# rgb_led.net
KiCad netlist of a schematic drawn in Altium Designer
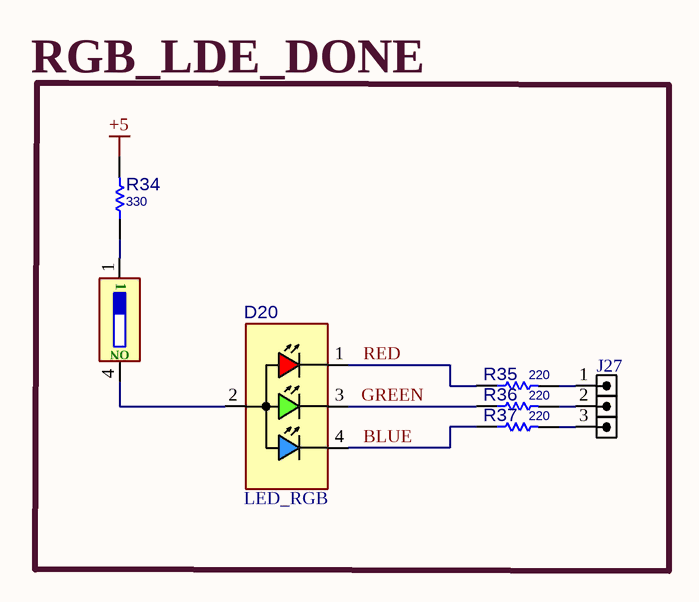
[diagram p0: rgb_led.SchDoc]

(export (version "E")
  (design (tool "Eeschema 10.0.6"))
  (components
    (comp (ref "D20")
      (value "LED_RGB")
      (footprint "LED5RGB")
      (description "LED, THD, 5MM, RGB COMMON CATHODE")
      (fields (field (name "MANF_P#") "YSL-R596CR3G4B5C-C10") (field (name "MANF") "CHINA YOUNG"))
      (libsource (lib "led(diode)") (part "LED_THD_5MM_RGB_CA"))
    )
    (comp (ref "J27")
      (value "HDRM3")
      (footprint "HDR_M_1X3")
      (description "CONN, HEADER, Male, pitch: 2.54mm, 3POS")
      (libsource (lib "conn_header_2.54mm_st") (part "HDR_M_1X3"))
    )
    (comp (ref "R34")
      (value "330")
      (footprint "R025W_AX04")
      (description "RESISTOR, THD")
      (fields (field (name "MANF_P#") "RK73H1ETTP4701F") (field (name "MANF") "KOA SPEER"))
      (libsource (lib "passive_thd") (part "RES_THD"))
    )
    (comp (ref "R35")
      (value "220")
      (footprint "R025W_AX04")
      (description "RESISTOR, THD")
      (fields (field (name "MANF_P#") "RK73H1ETTP4701F") (field (name "MANF") "KOA SPEER"))
      (libsource (lib "passive_thd") (part "RES_THD"))
    )
    (comp (ref "R36")
      (value "220")
      (footprint "R025W_AX04")
      (description "RESISTOR, THD")
      (fields (field (name "MANF_P#") "RK73H1ETTP4701F") (field (name "MANF") "KOA SPEER"))
      (libsource (lib "passive_thd") (part "RES_THD"))
    )
    (comp (ref "R37")
      (value "220")
      (footprint "R025W_AX04")
      (description "RESISTOR, THD")
      (fields (field (name "MANF_P#") "RK73H1ETTP4701F") (field (name "MANF") "KOA SPEER"))
      (libsource (lib "passive_thd") (part "RES_THD"))
    )
    (comp (ref "S3")
      (value "DIPSW12")
      (footprint "DIPSW254T_1")
      (description "SWITCH, DIP, 12P, THD")
      (fields (field (name "MANF") "MANF") (field (name "MANF_P#") "MANF_P#"))
      (libsource (lib "switch_dip") (part "DIPSW254T_12P"))
    )
  )
  (nets
    (net (code "1") (name "+5") (class "Default")
      (node (ref "R34") (pin "2") (pinfunction "2_2") (pintype "passive"))
    )
    (net (code "2") (name "/BLUE") (class "Default")
      (node (ref "D20") (pin "4") (pinfunction "BLU_4") (pintype "passive"))
      (node (ref "R37") (pin "1") (pinfunction "1_1") (pintype "passive"))
    )
    (net (code "3") (name "/GREEN") (class "Default")
      (node (ref "D20") (pin "3") (pinfunction "GRN_3") (pintype "passive"))
      (node (ref "R36") (pin "1") (pinfunction "1_1") (pintype "passive"))
    )
    (net (code "4") (name "/RED") (class "Default")
      (node (ref "D20") (pin "1") (pinfunction "RED_1") (pintype "passive"))
      (node (ref "R35") (pin "1") (pinfunction "1_1") (pintype "passive"))
    )
    (net (code "5") (name "Net-(D20-C)") (class "Default")
      (node (ref "D20") (pin "2") (pinfunction "C_2") (pintype "passive"))
      (node (ref "S3") (pin "4") (pinfunction "B1_4") (pintype "passive"))
    )
    (net (code "6") (name "Net-(J27-Pad1)") (class "Default")
      (node (ref "J27") (pin "1") (pinfunction "1_1") (pintype "passive"))
      (node (ref "R35") (pin "2") (pinfunction "2_2") (pintype "passive"))
    )
    (net (code "7") (name "Net-(J27-Pad2)") (class "Default")
      (node (ref "J27") (pin "2") (pinfunction "2_2") (pintype "passive"))
      (node (ref "R36") (pin "2") (pinfunction "2_2") (pintype "passive"))
    )
    (net (code "8") (name "Net-(J27-Pad3)") (class "Default")
      (node (ref "J27") (pin "3") (pinfunction "3_3") (pintype "passive"))
      (node (ref "R37") (pin "2") (pinfunction "2_2") (pintype "passive"))
    )
    (net (code "9") (name "Net-(S3A-A1)") (class "Default")
      (node (ref "R34") (pin "1") (pinfunction "1_1") (pintype "passive"))
      (node (ref "S3") (pin "1") (pinfunction "A1_1") (pintype "passive"))
    )
  )
)
